# Controller.net
KiCad netlist of a schematic drawn in Altium Designer
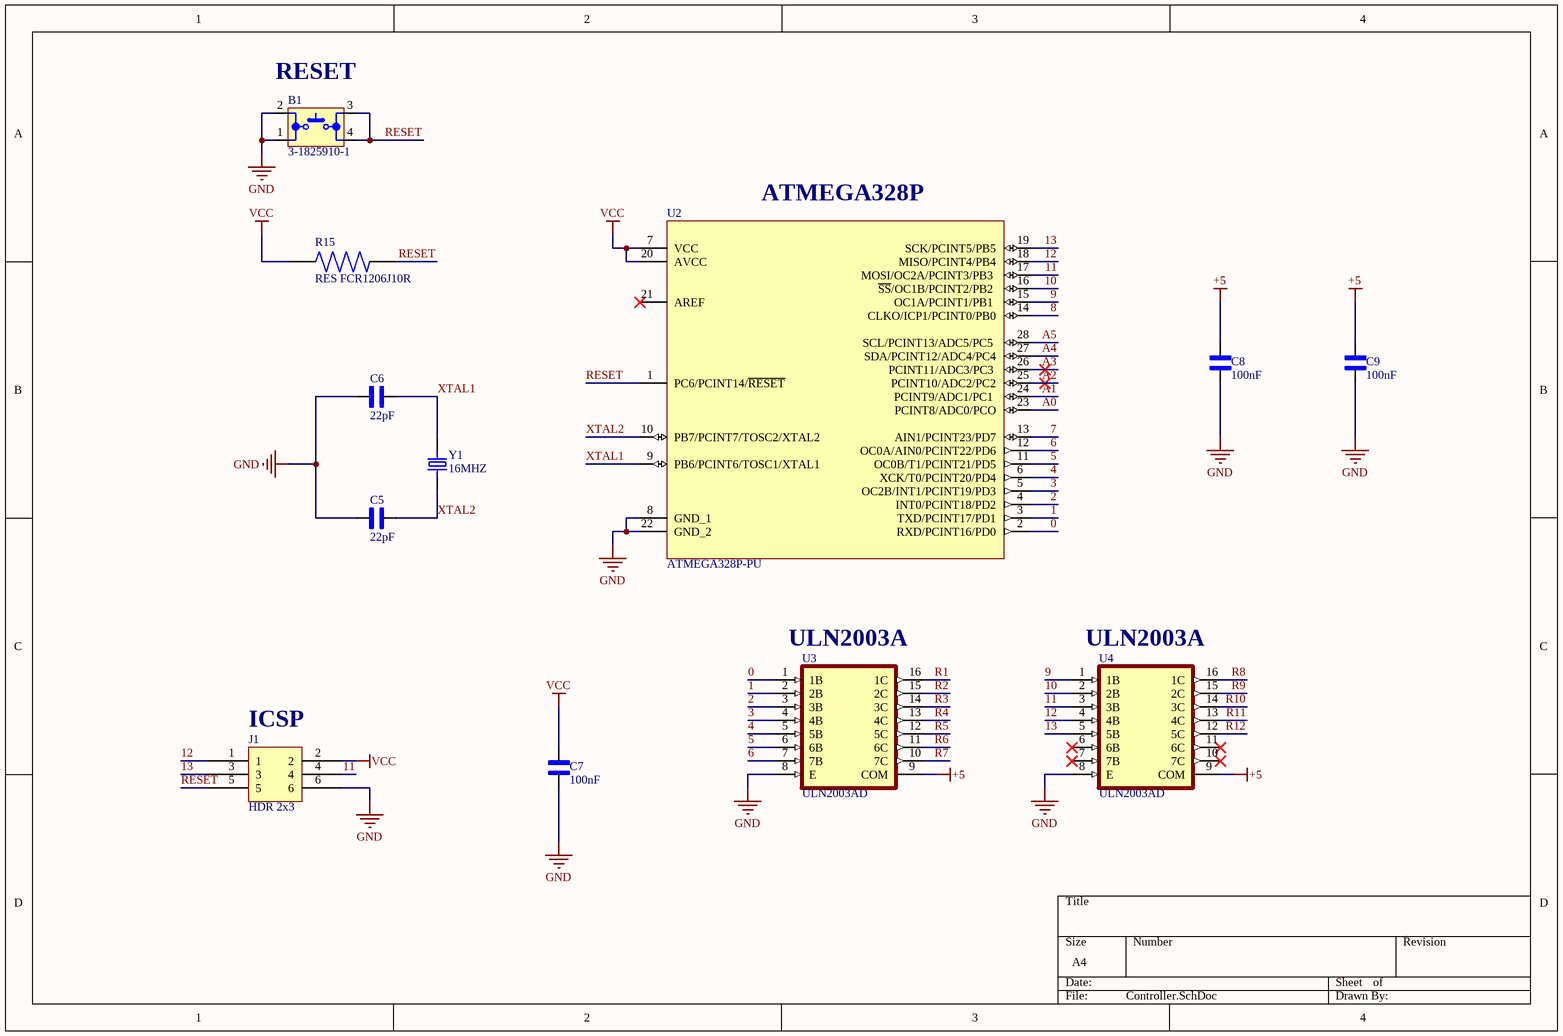
[diagram p0: Controller.SchDoc]

(export (version "E")
  (design (tool "Eeschema 10.0.6"))
  (components
    (comp (ref "B1")
      (value "3-1825910-1")
      (footprint "3-1825910-1")
      (description "Switch Push Button OFF (ON) SPST Round Button 0.05A 24VDC Momentary Contact PC Pins Thru-Hole")
      (fields
        (field (name "MANUFACTURER") "TE Connectivity Alcoswitch")
        (field (name "MANUFACTURER PART NUMBER") "1825910-6")
      )
      (libsource (lib "Ala Hassine v1.0") (part "3-1825910-1"))
    )
    (comp (ref "C5")
      (value "22pF")
      (footprint "0805Y0500220JCT")
      (description "22pF ±5% 50V Ceramic Capacitor C0G, NP0 (1B) 0805 (2012 Metric)")
      (fields (field (name "MF") "Syfer") (field (name "MP") "0805Y0500220JCT"))
      (libsource (lib "") (part "0805Y0500220JCT_1"))
    )
    (comp (ref "C6")
      (value "22pF")
      (footprint "0805Y0500220JCT")
      (description "22pF ±5% 50V Ceramic Capacitor C0G, NP0 (1B) 0805 (2012 Metric)")
      (fields (field (name "MF") "Syfer") (field (name "MP") "0805Y0500220JCT"))
      (libsource (lib "") (part "0805Y0500220JCT_1"))
    )
    (comp (ref "C7")
      (value "100nF")
      (footprint "0805Y0500220JCT")
      (description "22pF ±5% 50V Ceramic Capacitor C0G, NP0 (1B) 0805 (2012 Metric)")
      (fields (field (name "MF") "Syfer") (field (name "MP") "0805Y0500220JCT"))
      (libsource (lib "Ala Hassine v1.0") (part "0805Y0500220JCT"))
    )
    (comp (ref "C8")
      (value "100nF")
      (footprint "0805Y0500220JCT")
      (description "22pF ±5% 50V Ceramic Capacitor C0G, NP0 (1B) 0805 (2012 Metric)")
      (fields (field (name "MF") "Syfer") (field (name "MP") "0805Y0500220JCT"))
      (libsource (lib "Ala Hassine v1.0") (part "0805Y0500220JCT"))
    )
    (comp (ref "C9")
      (value "100nF")
      (footprint "0805Y0500220JCT")
      (description "22pF ±5% 50V Ceramic Capacitor C0G, NP0 (1B) 0805 (2012 Metric)")
      (fields (field (name "MF") "Syfer") (field (name "MP") "0805Y0500220JCT"))
      (libsource (lib "Ala Hassine v1.0") (part "0805Y0500220JCT"))
    )
    (comp (ref "J1")
      (value "HDR 2x3")
      (footprint "PIN Header Double Male 2x3")
      (description "PIN Header Double Male 2x3 TH Pitch 2.54mm")
      (libsource (lib "Ala Hassine v1.0") (part "PIN Header Double Male 2x3"))
    )
    (comp (ref "R15")
      (value "RES FCR1206J10R")
      (footprint "RES FCR1206J10R")
      (description "RES 1206 10 Ohm 5% 1/8W ±500ppm/°C Molded SMD SMD T/R")
      (fields (field (name "TOLERANCE") "5%") (field (name "MP") "FCR1206J10R"))
      (libsource (lib "Ala Hassine v1.0") (part "RES FCR1206J10R"))
    )
    (comp (ref "U2")
      (value "ATMEGA328P-PU")
      (footprint "ATMEGA328P-PU")
      (description "AVR ATMEGA Microcontroller IC 8-Bit 20MHz 32KB (16K x 16) FLASH 28-PDIP")
      (fields (field (name "MANUFACTURER") "Microchip"))
      (libsource (lib "Ala Hassine v1.0") (part "ATMEGA328P-PU"))
    )
    (comp (ref "U3")
      (value "ULN2003AD")
      (footprint "ULN2003AD")
      (description "50-V, 7-ch darlington transistor array, -20C to 70C")
      (fields (field (name "MF") "Texas Instruments"))
      (libsource (lib "Ala Hassine v1.0") (part "ULN2003AD"))
    )
    (comp (ref "U4")
      (value "ULN2003AD")
      (footprint "ULN2003AD")
      (description "50-V, 7-ch darlington transistor array, -20C to 70C")
      (fields (field (name "MF") "Texas Instruments"))
      (libsource (lib "Ala Hassine v1.0") (part "ULN2003AD"))
    )
    (comp (ref "Y1")
      (value "16MHZ")
      (footprint "ECS-160-20-3X-TR")
      (description "20 MHz ±30ppm Crystal Series 20pF 50 Ohms HC-49/US")
      (libsource (lib "Ala Hassine v1.0") (part "ECS-160-20-3X-TR"))
    )
  )
  (nets
    (net (code "1") (name "+5") (class "Default")
      (node (ref "C8") (pin "2") (pinfunction "2_2") (pintype "passive"))
      (node (ref "C9") (pin "2") (pinfunction "2_2") (pintype "passive"))
      (node (ref "U3") (pin "9") (pinfunction "COM_9") (pintype "power_in"))
      (node (ref "U4") (pin "9") (pinfunction "COM_9") (pintype "power_in"))
    )
    (net (code "2") (name "/0") (class "Default")
      (node (ref "U2") (pin "2") (pinfunction "RXD/PCINT16/PD0_2") (pintype "output"))
      (node (ref "U3") (pin "1") (pinfunction "1B_1") (pintype "input"))
    )
    (net (code "3") (name "/1") (class "Default")
      (node (ref "U2") (pin "3") (pinfunction "TXD/PCINT17/PD1_3") (pintype "output"))
      (node (ref "U3") (pin "2") (pinfunction "2B_2") (pintype "input"))
    )
    (net (code "4") (name "/2") (class "Default")
      (node (ref "U2") (pin "4") (pinfunction "INT0/PCINT18/PD2_4") (pintype "output"))
      (node (ref "U3") (pin "3") (pinfunction "3B_3") (pintype "input"))
    )
    (net (code "5") (name "/3") (class "Default")
      (node (ref "U2") (pin "5") (pinfunction "OC2B/INT1/PCINT19/PD3_5") (pintype "output"))
      (node (ref "U3") (pin "4") (pinfunction "4B_4") (pintype "input"))
    )
    (net (code "6") (name "/4") (class "Default")
      (node (ref "U2") (pin "6") (pinfunction "XCK/T0/PCINT20/PD4_6") (pintype "output"))
      (node (ref "U3") (pin "5") (pinfunction "5B_5") (pintype "input"))
    )
    (net (code "7") (name "/5") (class "Default")
      (node (ref "U2") (pin "11") (pinfunction "OC0B/T1/PCINT21/PD5_11") (pintype "output"))
      (node (ref "U3") (pin "6") (pinfunction "6B_6") (pintype "input"))
    )
    (net (code "8") (name "/6") (class "Default")
      (node (ref "U2") (pin "12") (pinfunction "OC0A/AIN0/PCINT22/PD6_12") (pintype "output"))
      (node (ref "U3") (pin "7") (pinfunction "7B_7") (pintype "input"))
    )
    (net (code "9") (name "/7") (class "Default")
      (node (ref "U2") (pin "13") (pinfunction "AIN1/PCINT23/PD7_13") (pintype "bidirectional"))
    )
    (net (code "10") (name "/8") (class "Default")
      (node (ref "U2") (pin "14") (pinfunction "CLKO/ICP1/PCINT0/PB0_14") (pintype "bidirectional"))
    )
    (net (code "11") (name "/9") (class "Default")
      (node (ref "U2") (pin "15") (pinfunction "OC1A/PCINT1/PB1_15") (pintype "bidirectional"))
      (node (ref "U4") (pin "1") (pinfunction "1B_1") (pintype "input"))
    )
    (net (code "12") (name "/10") (class "Default")
      (node (ref "U2") (pin "16") (pinfunction "~{SS}/OC1B/PCINT2/PB2_16") (pintype "bidirectional"))
      (node (ref "U4") (pin "2") (pinfunction "2B_2") (pintype "input"))
    )
    (net (code "13") (name "/11") (class "Default")
      (node (ref "J1") (pin "4") (pinfunction "4_4") (pintype "passive"))
      (node (ref "U2") (pin "17") (pinfunction "MOSI/OC2A/PCINT3/PB3_17") (pintype "bidirectional"))
      (node (ref "U4") (pin "3") (pinfunction "3B_3") (pintype "input"))
    )
    (net (code "14") (name "/12") (class "Default")
      (node (ref "J1") (pin "1") (pinfunction "1_1") (pintype "passive"))
      (node (ref "U2") (pin "18") (pinfunction "MISO/PCINT4/PB4_18") (pintype "bidirectional"))
      (node (ref "U4") (pin "4") (pinfunction "4B_4") (pintype "input"))
    )
    (net (code "15") (name "/13") (class "Default")
      (node (ref "J1") (pin "3") (pinfunction "3_3") (pintype "passive"))
      (node (ref "U2") (pin "19") (pinfunction "SCK/PCINT5/PB5_19") (pintype "bidirectional"))
      (node (ref "U4") (pin "5") (pinfunction "5B_5") (pintype "input"))
    )
    (net (code "16") (name "/A0") (class "Default")
      (node (ref "U2") (pin "23") (pinfunction "PCINT8/ADC0/PCO_23") (pintype "bidirectional"))
    )
    (net (code "17") (name "/A1") (class "Default")
      (node (ref "U2") (pin "24") (pinfunction "PCINT9/ADC1/PC1_24") (pintype "bidirectional"))
    )
    (net (code "18") (name "/A2") (class "Default")
      (node (ref "U2") (pin "25") (pinfunction "_PCINT10/ADC2/PC2_25") (pintype "bidirectional"))
    )
    (net (code "19") (name "/A3") (class "Default")
      (node (ref "U2") (pin "26") (pinfunction "PCINT11/ADC3/PC3_26") (pintype "bidirectional"))
    )
    (net (code "20") (name "/A4") (class "Default")
      (node (ref "U2") (pin "27") (pinfunction "SDA/PCINT12/ADC4/PC4_27") (pintype "bidirectional"))
    )
    (net (code "21") (name "/A5") (class "Default")
      (node (ref "U2") (pin "28") (pinfunction "SCL/PCINT13/ADC5/PC5_28") (pintype "bidirectional"))
    )
    (net (code "22") (name "/R1") (class "Default")
      (node (ref "U3") (pin "16") (pinfunction "1C_16") (pintype "output"))
    )
    (net (code "23") (name "/R2") (class "Default")
      (node (ref "U3") (pin "15") (pinfunction "2C_15") (pintype "output"))
    )
    (net (code "24") (name "/R3") (class "Default")
      (node (ref "U3") (pin "14") (pinfunction "3C_14") (pintype "output"))
    )
    (net (code "25") (name "/R4") (class "Default")
      (node (ref "U3") (pin "13") (pinfunction "4C_13") (pintype "output"))
    )
    (net (code "26") (name "/R5") (class "Default")
      (node (ref "U3") (pin "12") (pinfunction "5C_12") (pintype "output"))
    )
    (net (code "27") (name "/R6") (class "Default")
      (node (ref "U3") (pin "11") (pinfunction "6C_11") (pintype "output"))
    )
    (net (code "28") (name "/R7") (class "Default")
      (node (ref "U3") (pin "10") (pinfunction "7C_10") (pintype "output"))
    )
    (net (code "29") (name "/R8") (class "Default")
      (node (ref "U4") (pin "16") (pinfunction "1C_16") (pintype "output"))
    )
    (net (code "30") (name "/R9") (class "Default")
      (node (ref "U4") (pin "15") (pinfunction "2C_15") (pintype "output"))
    )
    (net (code "31") (name "/R10") (class "Default")
      (node (ref "U4") (pin "14") (pinfunction "3C_14") (pintype "output"))
    )
    (net (code "32") (name "/R11") (class "Default")
      (node (ref "U4") (pin "13") (pinfunction "4C_13") (pintype "output"))
    )
    (net (code "33") (name "/R12") (class "Default")
      (node (ref "U4") (pin "12") (pinfunction "5C_12") (pintype "output"))
    )
    (net (code "34") (name "/RESET") (class "Default")
      (node (ref "B1") (pin "3") (pinfunction "3_3") (pintype "passive"))
      (node (ref "B1") (pin "4") (pinfunction "4_4") (pintype "passive"))
      (node (ref "J1") (pin "5") (pinfunction "5_5") (pintype "passive"))
      (node (ref "R15") (pin "2") (pinfunction "2_2") (pintype "passive"))
      (node (ref "U2") (pin "1") (pinfunction "PC6/PCINT14/~{RESET}_1") (pintype "passive"))
    )
    (net (code "35") (name "/XTAL1") (class "Default")
      (node (ref "C6") (pin "2") (pinfunction "2_2") (pintype "passive"))
      (node (ref "U2") (pin "9") (pinfunction "PB6/PCINT6/TOSC1/XTAL1_9") (pintype "bidirectional"))
      (node (ref "Y1") (pin "2") (pinfunction "2_2") (pintype "passive"))
    )
    (net (code "36") (name "/XTAL2") (class "Default")
      (node (ref "C5") (pin "2") (pinfunction "2_2") (pintype "passive"))
      (node (ref "U2") (pin "10") (pinfunction "PB7/PCINT7/TOSC2/XTAL2_10") (pintype "bidirectional"))
      (node (ref "Y1") (pin "1") (pinfunction "1_1") (pintype "passive"))
    )
    (net (code "37") (name "GND") (class "Default")
      (node (ref "B1") (pin "1") (pinfunction "1_1") (pintype "passive"))
      (node (ref "B1") (pin "2") (pinfunction "2_2") (pintype "passive"))
      (node (ref "C5") (pin "1") (pinfunction "1_1") (pintype "passive"))
      (node (ref "C6") (pin "1") (pinfunction "1_1") (pintype "passive"))
      (node (ref "C7") (pin "1") (pinfunction "1_1") (pintype "passive"))
      (node (ref "C8") (pin "1") (pinfunction "1_1") (pintype "passive"))
      (node (ref "C9") (pin "1") (pinfunction "1_1") (pintype "passive"))
      (node (ref "J1") (pin "6") (pinfunction "6_6") (pintype "passive"))
      (node (ref "U2") (pin "22") (pinfunction "GND_2_22") (pintype "passive"))
      (node (ref "U2") (pin "8") (pinfunction "GND_1_8") (pintype "passive"))
      (node (ref "U3") (pin "8") (pinfunction "E_8") (pintype "input"))
      (node (ref "U4") (pin "8") (pinfunction "E_8") (pintype "input"))
    )
    (net (code "38") (name "VCC") (class "Default")
      (node (ref "C7") (pin "2") (pinfunction "2_2") (pintype "passive"))
      (node (ref "J1") (pin "2") (pinfunction "2_2") (pintype "passive"))
      (node (ref "R15") (pin "1") (pinfunction "1_1") (pintype "passive"))
      (node (ref "U2") (pin "20") (pinfunction "AVCC_20") (pintype "passive"))
      (node (ref "U2") (pin "7") (pinfunction "VCC_7") (pintype "passive"))
    )
    (net (code "39") (name "unconnected-(U2-AREF-Pad21)") (class "Default")
      (node (ref "U2") (pin "21") (pinfunction "AREF_21") (pintype "passive+no_connect"))
    )
    (net (code "40") (name "unconnected-(U4-6B-Pad6)") (class "Default")
      (node (ref "U4") (pin "6") (pinfunction "6B_6") (pintype "input+no_connect"))
    )
    (net (code "41") (name "unconnected-(U4-6C-Pad11)") (class "Default")
      (node (ref "U4") (pin "11") (pinfunction "6C_11") (pintype "output+no_connect"))
    )
    (net (code "42") (name "unconnected-(U4-7B-Pad7)") (class "Default")
      (node (ref "U4") (pin "7") (pinfunction "7B_7") (pintype "input+no_connect"))
    )
    (net (code "43") (name "unconnected-(U4-7C-Pad10)") (class "Default")
      (node (ref "U4") (pin "10") (pinfunction "7C_10") (pintype "output+no_connect"))
    )
  )
)
